# usb_serial_daughter.net
KiCad netlist of a schematic drawn in Altium Designer
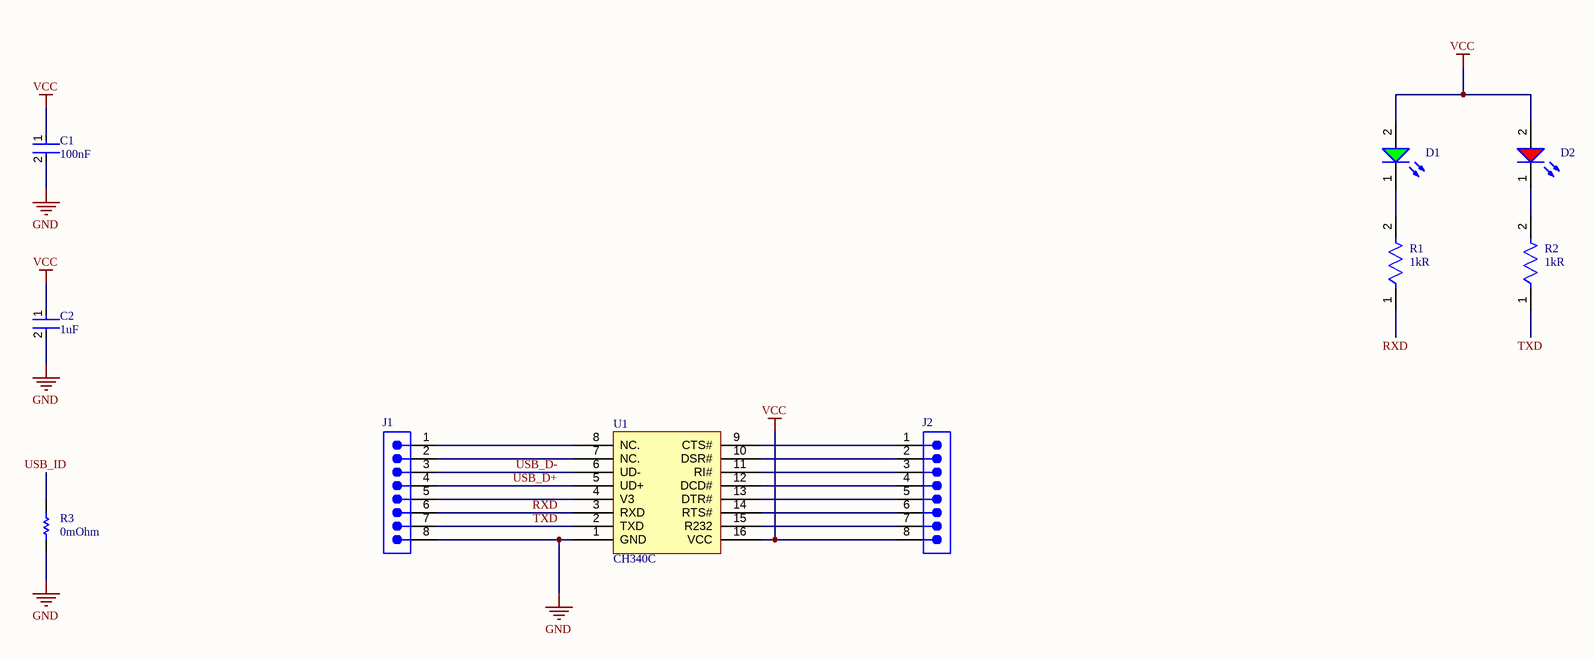
[diagram p0: usb_serial_daughter.SchDoc]

(export (version "E")
  (design (tool "Eeschema 10.0.6"))
  (components
    (comp (ref "C1")
      (value "0402ZD104KAT2A")
      (footprint "FP-0402-L_1_0_1-W_0_5_0_1-IPC_C")
      (description "General Purpose Ceramic Capacitor, 0402, 100nF, 10%, X5R, 15%, 10V")
      (fields
        (field (name "VOLTAGE") "10V")
        (field (name "TOLERANCE") "10%")
        (field (name "CAPACITANCE") "100nF")
      )
      (libsource (lib "Altium Content Vault") (part "b4654b650e69147ec39a6b967a45e02"))
    )
    (comp (ref "C2")
      (value "EMK105BJ105KV-F")
      (footprint "FP-0402-L_1_0_0_05-W_0_5-IPC_A")
      (description "None")
      (fields (field (name "TOLERANCE") "10%") (field (name "CAPACITANCE") "1uF"))
      (libsource (lib "Altium Content Vault") (part "b4654b650e69147ec39a6b967a45e02"))
    )
    (comp (ref "D1")
      (value "150060VS75000")
      (footprint "WL-SMCW_0603_150060xx75000")
      (description "WURTH ELEKTRONIK - 150060VS75000 - LED, Green, SMD, 0603, 30 mA, 2 V, 570 nm")
      (libsource (lib "Altium Content Vault") (part "LED_Green_2A-1K"))
    )
    (comp (ref "D2")
      (value "150060RS75000")
      (footprint "WL-SMCW_0603_150060xx75000")
      (description "LED Low-Power Uni-Color Red 630nm 2V 2-Pin Chip 0603(1608Metric) T/R")
      (libsource (lib "Altium Content Vault") (part "LED_Red_2A-1K"))
    )
    (comp (ref "J1")
      (value "61300811121")
      (footprint "61300811121")
      (libsource (lib "Altium Content Vault") (part "Header_Male_1R_08P"))
    )
    (comp (ref "J2")
      (value "61300811121")
      (footprint "61300811121")
      (libsource (lib "Altium Content Vault") (part "Header_Male_1R_08P"))
    )
    (comp (ref "R1")
      (value "RMCF0402FT1K00")
      (footprint "FP-RMCF0402-IPC_A")
      (description "1kΩ ±1% 0.063W 0402 Thick Film Chip Resistor AEC-Q200 compliant")
      (fields (field (name "TOLERANCE") "1%") (field (name "RESISTANCE") "1kR"))
      (libsource (lib "Altium Content Vault") (part "1029c3af85768c4190bb7ad29bc67b5"))
    )
    (comp (ref "R2")
      (value "RMCF0402FT1K00")
      (footprint "FP-RMCF0402-IPC_A")
      (description "1kΩ ±1% 0.063W 0402 Thick Film Chip Resistor AEC-Q200 compliant")
      (fields (field (name "TOLERANCE") "1%") (field (name "RESISTANCE") "1kR"))
      (libsource (lib "Altium Content Vault") (part "1029c3af85768c4190bb7ad29bc67b5"))
    )
    (comp (ref "R3")
      (value "ERJ2GE0R00X")
      (footprint "RESC1005X40X25LL05T05")
      (description "Chip Resistor, 0 Ohm, 0.1 W, -55 to 155 degC, 0402 (1005 Metric), RoHS, Tape and Reel")
      (fields
        (field (name "MANUFACTURER") "Panasonic")
        (field (name "RESISTANCE") "0mOhm")
        (field (name "TOLERANCE") "5%")
      )
      (libsource (lib "Altium Content Vault") (part "RES-2"))
    )
    (comp (ref "U1")
      (value "CH340C")
      (footprint "CH340C")
      (description "USB to Serial CH340 IC")
      (libsource (lib "RAK3172_RF_Generator") (part "CH340C"))
    )
  )
  (nets
    (net (code "1") (name "/RXD") (class "Default")
      (node (ref "J1") (pin "6") (pinfunction "6_6") (pintype "passive"))
      (node (ref "R1") (pin "1") (pinfunction "1_1") (pintype "passive"))
      (node (ref "U1") (pin "3") (pinfunction "RXD_3") (pintype "passive"))
    )
    (net (code "2") (name "/TXD") (class "Default")
      (node (ref "J1") (pin "7") (pinfunction "7_7") (pintype "passive"))
      (node (ref "R2") (pin "1") (pinfunction "1_1") (pintype "passive"))
      (node (ref "U1") (pin "2") (pinfunction "TXD_2") (pintype "passive"))
    )
    (net (code "3") (name "/USB_D+") (class "Default")
      (node (ref "J1") (pin "4") (pinfunction "4_4") (pintype "passive"))
      (node (ref "U1") (pin "5") (pinfunction "UD+_5") (pintype "passive"))
    )
    (net (code "4") (name "/USB_D-") (class "Default")
      (node (ref "J1") (pin "3") (pinfunction "3_3") (pintype "passive"))
      (node (ref "U1") (pin "6") (pinfunction "UD-_6") (pintype "passive"))
    )
    (net (code "5") (name "/USB_ID") (class "Default")
      (node (ref "R3") (pin "2") (pinfunction "2_2") (pintype "passive"))
    )
    (net (code "6") (name "GND") (class "Default")
      (node (ref "C1") (pin "2") (pinfunction "2_2") (pintype "passive"))
      (node (ref "C2") (pin "2") (pinfunction "2_2") (pintype "passive"))
      (node (ref "J1") (pin "8") (pinfunction "8_8") (pintype "passive"))
      (node (ref "R3") (pin "1") (pinfunction "1_1") (pintype "passive"))
      (node (ref "U1") (pin "1") (pinfunction "GND_1") (pintype "passive"))
    )
    (net (code "7") (name "Net-(D1-K)") (class "Default")
      (node (ref "D1") (pin "1") (pinfunction "K_1") (pintype "passive"))
      (node (ref "R1") (pin "2") (pinfunction "2_2") (pintype "passive"))
    )
    (net (code "8") (name "Net-(D2-K)") (class "Default")
      (node (ref "D2") (pin "1") (pinfunction "K_1") (pintype "passive"))
      (node (ref "R2") (pin "2") (pinfunction "2_2") (pintype "passive"))
    )
    (net (code "9") (name "Net-(J1-Pad1)") (class "Default")
      (node (ref "J1") (pin "1") (pinfunction "1_1") (pintype "passive"))
      (node (ref "U1") (pin "8") (pinfunction "NC._8") (pintype "passive"))
    )
    (net (code "10") (name "Net-(J1-Pad2)") (class "Default")
      (node (ref "J1") (pin "2") (pinfunction "2_2") (pintype "passive"))
      (node (ref "U1") (pin "7") (pinfunction "NC._7") (pintype "passive"))
    )
    (net (code "11") (name "Net-(U1-CTS#)") (class "Default")
      (node (ref "J2") (pin "1") (pinfunction "1_1") (pintype "passive"))
      (node (ref "U1") (pin "9") (pinfunction "CTS#_9") (pintype "passive"))
    )
    (net (code "12") (name "Net-(U1-DCD#)") (class "Default")
      (node (ref "J2") (pin "4") (pinfunction "4_4") (pintype "passive"))
      (node (ref "U1") (pin "12") (pinfunction "DCD#_12") (pintype "passive"))
    )
    (net (code "13") (name "Net-(U1-DSR#)") (class "Default")
      (node (ref "J2") (pin "2") (pinfunction "2_2") (pintype "passive"))
      (node (ref "U1") (pin "10") (pinfunction "DSR#_10") (pintype "passive"))
    )
    (net (code "14") (name "Net-(U1-DTR#)") (class "Default")
      (node (ref "J2") (pin "5") (pinfunction "5_5") (pintype "passive"))
      (node (ref "U1") (pin "13") (pinfunction "DTR#_13") (pintype "passive"))
    )
    (net (code "15") (name "Net-(U1-R232)") (class "Default")
      (node (ref "J2") (pin "7") (pinfunction "7_7") (pintype "passive"))
      (node (ref "U1") (pin "15") (pinfunction "R232_15") (pintype "passive"))
    )
    (net (code "16") (name "Net-(U1-RI#)") (class "Default")
      (node (ref "J2") (pin "3") (pinfunction "3_3") (pintype "passive"))
      (node (ref "U1") (pin "11") (pinfunction "RI#_11") (pintype "passive"))
    )
    (net (code "17") (name "Net-(U1-RTS#)") (class "Default")
      (node (ref "J2") (pin "6") (pinfunction "6_6") (pintype "passive"))
      (node (ref "U1") (pin "14") (pinfunction "RTS#_14") (pintype "passive"))
    )
    (net (code "18") (name "Net-(U1-V3)") (class "Default")
      (node (ref "J1") (pin "5") (pinfunction "5_5") (pintype "passive"))
      (node (ref "U1") (pin "4") (pinfunction "V3_4") (pintype "passive"))
    )
    (net (code "19") (name "VCC") (class "Default")
      (node (ref "C1") (pin "1") (pinfunction "1_1") (pintype "passive"))
      (node (ref "C2") (pin "1") (pinfunction "1_1") (pintype "passive"))
      (node (ref "D1") (pin "2") (pinfunction "A_2") (pintype "passive"))
      (node (ref "D2") (pin "2") (pinfunction "A_2") (pintype "passive"))
      (node (ref "J2") (pin "8") (pinfunction "8_8") (pintype "passive"))
      (node (ref "U1") (pin "16") (pinfunction "VCC_16") (pintype "passive"))
    )
  )
)
